# decaslime_mainboard_sch_easyeda.net
KiCad netlist of a schematic drawn in EasyEDA
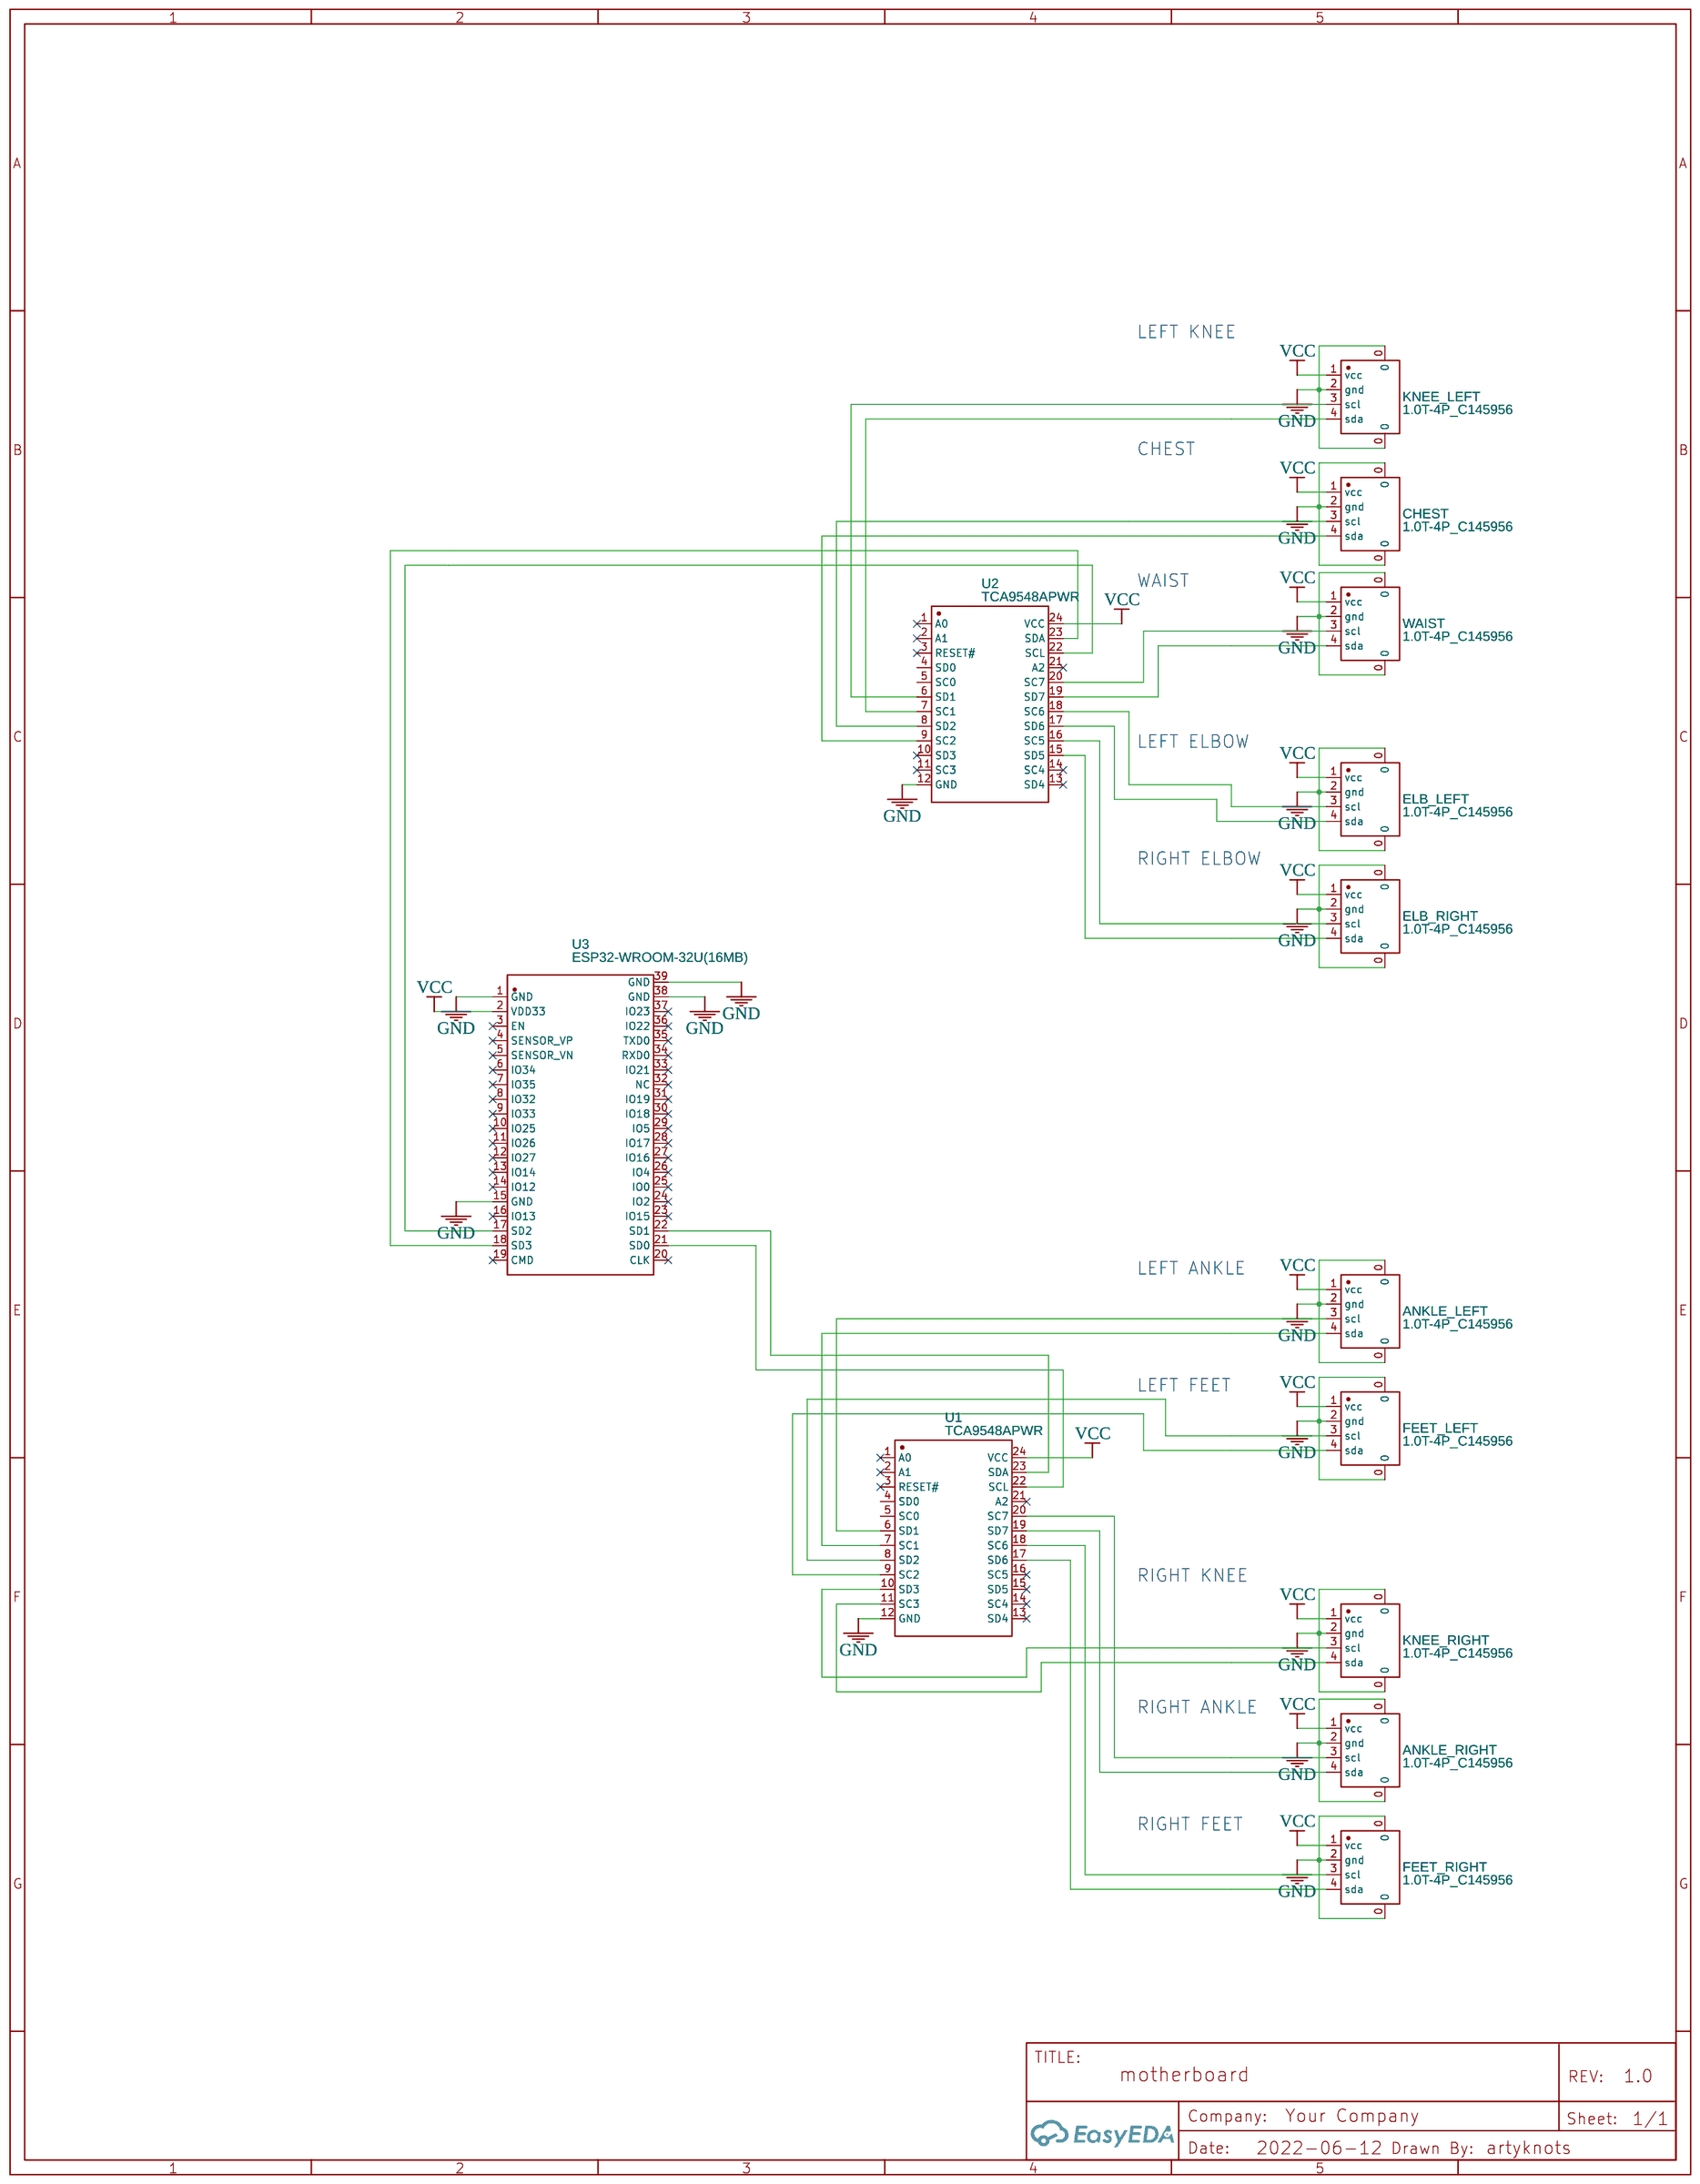
[diagram p0: schematic sheet]

(export (version "E")
  (design (tool "Eeschema 10.0.6"))
  (components
    (comp (ref "ANKLE_LEFT")
      (value "1.0T-4P_C145956")
      (fields (field (name "BOM_Supplier Part") "C145956"))
      (libsource (lib "") (part "1.0T-4P_C145956_7"))
    )
    (comp (ref "ANKLE_RIGHT")
      (value "1.0T-4P_C145956")
      (fields (field (name "BOM_Supplier Part") "C145956"))
      (libsource (lib "") (part "1.0T-4P_C145956_1"))
    )
    (comp (ref "CHEST")
      (value "1.0T-4P_C145956")
      (fields (field (name "BOM_Supplier Part") "C145956"))
      (libsource (lib "") (part "1.0T-4P_C145956_6"))
    )
    (comp (ref "ELB_LEFT")
      (value "1.0T-4P_C145956")
      (fields (field (name "BOM_Supplier Part") "C145956"))
      (libsource (lib "") (part "1.0T-4P_C145956"))
    )
    (comp (ref "ELB_RIGHT")
      (value "1.0T-4P_C145956")
      (fields (field (name "BOM_Supplier Part") "C145956"))
      (libsource (lib "") (part "1.0T-4P_C145956_5"))
    )
    (comp (ref "FEET_LEFT")
      (value "1.0T-4P_C145956")
      (fields (field (name "BOM_Supplier Part") "C145956"))
      (libsource (lib "") (part "1.0T-4P_C145956_2"))
    )
    (comp (ref "FEET_RIGHT")
      (value "1.0T-4P_C145956")
      (fields (field (name "BOM_Supplier Part") "C145956"))
      (libsource (lib "") (part "1.0T-4P_C145956_8"))
    )
    (comp (ref "KNEE_LEFT")
      (value "1.0T-4P_C145956")
      (fields (field (name "BOM_Supplier Part") "C145956"))
      (libsource (lib "") (part "1.0T-4P_C145956_3"))
    )
    (comp (ref "KNEE_RIGHT")
      (value "1.0T-4P_C145956")
      (fields (field (name "BOM_Supplier Part") "C145956"))
      (libsource (lib "") (part "1.0T-4P_C145956_9"))
    )
    (comp (ref "U1")
      (value "TCA9548APWR")
      (fields (field (name "BOM_Supplier Part") "C130026"))
      (libsource (lib "") (part "TCA9548APWR"))
    )
    (comp (ref "U2")
      (value "TCA9548APWR")
      (fields (field (name "BOM_Supplier Part") "C130026"))
      (libsource (lib "") (part "TCA9548APWR"))
    )
    (comp (ref "U3")
      (value "ESP32-WROOM-32U(16MB)")
      (fields (field (name "BOM_Supplier Part") "C529580"))
      (libsource (lib "") (part "ESP32-WROOM-32U(16MB)"))
    )
    (comp (ref "WAIST")
      (value "1.0T-4P_C145956")
      (fields (field (name "BOM_Supplier Part") "C145956"))
      (libsource (lib "") (part "1.0T-4P_C145956_4"))
    )
  )
  (nets
    (net (code "1") (name "GND") (class "Default")
      (node (ref "ANKLE_LEFT") (pin "0") (pinfunction "0_0") (pintype "unspecified"))
      (node (ref "ANKLE_LEFT") (pin "2") (pinfunction "gnd_2") (pintype "unspecified"))
      (node (ref "ANKLE_RIGHT") (pin "0") (pinfunction "0_0") (pintype "unspecified"))
      (node (ref "ANKLE_RIGHT") (pin "2") (pinfunction "gnd_2") (pintype "unspecified"))
      (node (ref "CHEST") (pin "0") (pinfunction "0_0") (pintype "unspecified"))
      (node (ref "CHEST") (pin "2") (pinfunction "gnd_2") (pintype "unspecified"))
      (node (ref "ELB_LEFT") (pin "0") (pinfunction "0_0") (pintype "unspecified"))
      (node (ref "ELB_LEFT") (pin "2") (pinfunction "gnd_2") (pintype "unspecified"))
      (node (ref "ELB_RIGHT") (pin "0") (pinfunction "0_0") (pintype "unspecified"))
      (node (ref "ELB_RIGHT") (pin "2") (pinfunction "gnd_2") (pintype "unspecified"))
      (node (ref "FEET_LEFT") (pin "0") (pinfunction "0_0") (pintype "unspecified"))
      (node (ref "FEET_LEFT") (pin "2") (pinfunction "gnd_2") (pintype "unspecified"))
      (node (ref "FEET_RIGHT") (pin "0") (pinfunction "0_0") (pintype "unspecified"))
      (node (ref "FEET_RIGHT") (pin "2") (pinfunction "gnd_2") (pintype "unspecified"))
      (node (ref "KNEE_LEFT") (pin "0") (pinfunction "0_0") (pintype "unspecified"))
      (node (ref "KNEE_LEFT") (pin "2") (pinfunction "gnd_2") (pintype "unspecified"))
      (node (ref "KNEE_RIGHT") (pin "0") (pinfunction "0_0") (pintype "unspecified"))
      (node (ref "KNEE_RIGHT") (pin "2") (pinfunction "gnd_2") (pintype "unspecified"))
      (node (ref "U1") (pin "12") (pinfunction "GND_12") (pintype "unspecified"))
      (node (ref "U2") (pin "12") (pinfunction "GND_12") (pintype "unspecified"))
      (node (ref "U3") (pin "1") (pinfunction "GND_1") (pintype "unspecified"))
      (node (ref "U3") (pin "15") (pinfunction "GND_15") (pintype "unspecified"))
      (node (ref "U3") (pin "38") (pinfunction "GND_38") (pintype "unspecified"))
      (node (ref "U3") (pin "39") (pinfunction "GND_39") (pintype "unspecified"))
      (node (ref "WAIST") (pin "0") (pinfunction "0_0") (pintype "unspecified"))
      (node (ref "WAIST") (pin "2") (pinfunction "gnd_2") (pintype "unspecified"))
    )
    (net (code "2") (name "Net-(ANKLE_LEFT-scl)") (class "Default")
      (node (ref "ANKLE_LEFT") (pin "3") (pinfunction "scl_3") (pintype "unspecified"))
      (node (ref "U1") (pin "6") (pinfunction "SD1_6") (pintype "unspecified"))
    )
    (net (code "3") (name "Net-(ANKLE_LEFT-sda)") (class "Default")
      (node (ref "ANKLE_LEFT") (pin "4") (pinfunction "sda_4") (pintype "unspecified"))
      (node (ref "U1") (pin "7") (pinfunction "SC1_7") (pintype "unspecified"))
    )
    (net (code "4") (name "Net-(ANKLE_RIGHT-scl)") (class "Default")
      (node (ref "ANKLE_RIGHT") (pin "3") (pinfunction "scl_3") (pintype "unspecified"))
      (node (ref "U1") (pin "20") (pinfunction "SC7_20") (pintype "unspecified"))
    )
    (net (code "5") (name "Net-(ANKLE_RIGHT-sda)") (class "Default")
      (node (ref "ANKLE_RIGHT") (pin "4") (pinfunction "sda_4") (pintype "unspecified"))
      (node (ref "U1") (pin "19") (pinfunction "SD7_19") (pintype "unspecified"))
    )
    (net (code "6") (name "Net-(CHEST-scl)") (class "Default")
      (node (ref "CHEST") (pin "3") (pinfunction "scl_3") (pintype "unspecified"))
      (node (ref "U2") (pin "8") (pinfunction "SD2_8") (pintype "unspecified"))
    )
    (net (code "7") (name "Net-(CHEST-sda)") (class "Default")
      (node (ref "CHEST") (pin "4") (pinfunction "sda_4") (pintype "unspecified"))
      (node (ref "U2") (pin "9") (pinfunction "SC2_9") (pintype "unspecified"))
    )
    (net (code "8") (name "Net-(ELB_LEFT-scl)") (class "Default")
      (node (ref "ELB_LEFT") (pin "3") (pinfunction "scl_3") (pintype "unspecified"))
      (node (ref "U2") (pin "18") (pinfunction "SC6_18") (pintype "unspecified"))
    )
    (net (code "9") (name "Net-(ELB_LEFT-sda)") (class "Default")
      (node (ref "ELB_LEFT") (pin "4") (pinfunction "sda_4") (pintype "unspecified"))
      (node (ref "U2") (pin "17") (pinfunction "SD6_17") (pintype "unspecified"))
    )
    (net (code "10") (name "Net-(ELB_RIGHT-scl)") (class "Default")
      (node (ref "ELB_RIGHT") (pin "3") (pinfunction "scl_3") (pintype "unspecified"))
      (node (ref "U2") (pin "16") (pinfunction "SC5_16") (pintype "unspecified"))
    )
    (net (code "11") (name "Net-(ELB_RIGHT-sda)") (class "Default")
      (node (ref "ELB_RIGHT") (pin "4") (pinfunction "sda_4") (pintype "unspecified"))
      (node (ref "U2") (pin "15") (pinfunction "SD5_15") (pintype "unspecified"))
    )
    (net (code "12") (name "Net-(FEET_LEFT-scl)") (class "Default")
      (node (ref "FEET_LEFT") (pin "3") (pinfunction "scl_3") (pintype "unspecified"))
      (node (ref "U1") (pin "8") (pinfunction "SD2_8") (pintype "unspecified"))
    )
    (net (code "13") (name "Net-(FEET_LEFT-sda)") (class "Default")
      (node (ref "FEET_LEFT") (pin "4") (pinfunction "sda_4") (pintype "unspecified"))
      (node (ref "U1") (pin "9") (pinfunction "SC2_9") (pintype "unspecified"))
    )
    (net (code "14") (name "Net-(FEET_RIGHT-scl)") (class "Default")
      (node (ref "FEET_RIGHT") (pin "3") (pinfunction "scl_3") (pintype "unspecified"))
      (node (ref "U1") (pin "18") (pinfunction "SC6_18") (pintype "unspecified"))
    )
    (net (code "15") (name "Net-(FEET_RIGHT-sda)") (class "Default")
      (node (ref "FEET_RIGHT") (pin "4") (pinfunction "sda_4") (pintype "unspecified"))
      (node (ref "U1") (pin "17") (pinfunction "SD6_17") (pintype "unspecified"))
    )
    (net (code "16") (name "Net-(KNEE_LEFT-scl)") (class "Default")
      (node (ref "KNEE_LEFT") (pin "3") (pinfunction "scl_3") (pintype "unspecified"))
      (node (ref "U2") (pin "6") (pinfunction "SD1_6") (pintype "unspecified"))
    )
    (net (code "17") (name "Net-(KNEE_LEFT-sda)") (class "Default")
      (node (ref "KNEE_LEFT") (pin "4") (pinfunction "sda_4") (pintype "unspecified"))
      (node (ref "U2") (pin "7") (pinfunction "SC1_7") (pintype "unspecified"))
    )
    (net (code "18") (name "Net-(KNEE_RIGHT-scl)") (class "Default")
      (node (ref "KNEE_RIGHT") (pin "3") (pinfunction "scl_3") (pintype "unspecified"))
      (node (ref "U1") (pin "10") (pinfunction "SD3_10") (pintype "unspecified"))
    )
    (net (code "19") (name "Net-(KNEE_RIGHT-sda)") (class "Default")
      (node (ref "KNEE_RIGHT") (pin "4") (pinfunction "sda_4") (pintype "unspecified"))
      (node (ref "U1") (pin "11") (pinfunction "SC3_11") (pintype "unspecified"))
    )
    (net (code "20") (name "Net-(U1-SCL)") (class "Default")
      (node (ref "U1") (pin "22") (pinfunction "SCL_22") (pintype "unspecified"))
      (node (ref "U3") (pin "21") (pinfunction "SD0_21") (pintype "unspecified"))
    )
    (net (code "21") (name "Net-(U1-SDA)") (class "Default")
      (node (ref "U1") (pin "23") (pinfunction "SDA_23") (pintype "unspecified"))
      (node (ref "U3") (pin "22") (pinfunction "SD1_22") (pintype "unspecified"))
    )
    (net (code "22") (name "Net-(U2-SC7)") (class "Default")
      (node (ref "U2") (pin "20") (pinfunction "SC7_20") (pintype "unspecified"))
      (node (ref "WAIST") (pin "3") (pinfunction "scl_3") (pintype "unspecified"))
    )
    (net (code "23") (name "Net-(U2-SCL)") (class "Default")
      (node (ref "U2") (pin "22") (pinfunction "SCL_22") (pintype "unspecified"))
      (node (ref "U3") (pin "17") (pinfunction "SD2_17") (pintype "unspecified"))
    )
    (net (code "24") (name "Net-(U2-SD7)") (class "Default")
      (node (ref "U2") (pin "19") (pinfunction "SD7_19") (pintype "unspecified"))
      (node (ref "WAIST") (pin "4") (pinfunction "sda_4") (pintype "unspecified"))
    )
    (net (code "25") (name "Net-(U2-SDA)") (class "Default")
      (node (ref "U2") (pin "23") (pinfunction "SDA_23") (pintype "unspecified"))
      (node (ref "U3") (pin "18") (pinfunction "SD3_18") (pintype "unspecified"))
    )
    (net (code "26") (name "VCC") (class "Default")
      (node (ref "ANKLE_LEFT") (pin "1") (pinfunction "vcc_1") (pintype "unspecified"))
      (node (ref "ANKLE_RIGHT") (pin "1") (pinfunction "vcc_1") (pintype "unspecified"))
      (node (ref "CHEST") (pin "1") (pinfunction "vcc_1") (pintype "unspecified"))
      (node (ref "ELB_LEFT") (pin "1") (pinfunction "vcc_1") (pintype "unspecified"))
      (node (ref "ELB_RIGHT") (pin "1") (pinfunction "vcc_1") (pintype "unspecified"))
      (node (ref "FEET_LEFT") (pin "1") (pinfunction "vcc_1") (pintype "unspecified"))
      (node (ref "FEET_RIGHT") (pin "1") (pinfunction "vcc_1") (pintype "unspecified"))
      (node (ref "KNEE_LEFT") (pin "1") (pinfunction "vcc_1") (pintype "unspecified"))
      (node (ref "KNEE_RIGHT") (pin "1") (pinfunction "vcc_1") (pintype "unspecified"))
      (node (ref "U1") (pin "24") (pinfunction "VCC_24") (pintype "unspecified"))
      (node (ref "U2") (pin "24") (pinfunction "VCC_24") (pintype "unspecified"))
      (node (ref "U3") (pin "2") (pinfunction "VDD33_2") (pintype "unspecified"))
      (node (ref "WAIST") (pin "1") (pinfunction "vcc_1") (pintype "unspecified"))
    )
    (net (code "27") (name "unconnected-(U1-A0-Pad1)") (class "Default")
      (node (ref "U1") (pin "1") (pinfunction "A0_1") (pintype "unspecified+no_connect"))
    )
    (net (code "28") (name "unconnected-(U1-A1-Pad2)") (class "Default")
      (node (ref "U1") (pin "2") (pinfunction "A1_2") (pintype "unspecified+no_connect"))
    )
    (net (code "29") (name "unconnected-(U1-A2-Pad21)") (class "Default")
      (node (ref "U1") (pin "21") (pinfunction "A2_21") (pintype "unspecified+no_connect"))
    )
    (net (code "30") (name "unconnected-(U1-RESET#-Pad3)") (class "Default")
      (node (ref "U1") (pin "3") (pinfunction "RESET#_3") (pintype "unspecified+no_connect"))
    )
    (net (code "31") (name "unconnected-(U1-SC0-Pad5)") (class "Default")
      (node (ref "U1") (pin "5") (pinfunction "SC0_5") (pintype "unspecified"))
    )
    (net (code "32") (name "unconnected-(U1-SC4-Pad14)") (class "Default")
      (node (ref "U1") (pin "14") (pinfunction "SC4_14") (pintype "unspecified+no_connect"))
    )
    (net (code "33") (name "unconnected-(U1-SC5-Pad16)") (class "Default")
      (node (ref "U1") (pin "16") (pinfunction "SC5_16") (pintype "unspecified+no_connect"))
    )
    (net (code "34") (name "unconnected-(U1-SD0-Pad4)") (class "Default")
      (node (ref "U1") (pin "4") (pinfunction "SD0_4") (pintype "unspecified"))
    )
    (net (code "35") (name "unconnected-(U1-SD4-Pad13)") (class "Default")
      (node (ref "U1") (pin "13") (pinfunction "SD4_13") (pintype "unspecified+no_connect"))
    )
    (net (code "36") (name "unconnected-(U1-SD5-Pad15)") (class "Default")
      (node (ref "U1") (pin "15") (pinfunction "SD5_15") (pintype "unspecified+no_connect"))
    )
    (net (code "37") (name "unconnected-(U2-A0-Pad1)") (class "Default")
      (node (ref "U2") (pin "1") (pinfunction "A0_1") (pintype "unspecified+no_connect"))
    )
    (net (code "38") (name "unconnected-(U2-A1-Pad2)") (class "Default")
      (node (ref "U2") (pin "2") (pinfunction "A1_2") (pintype "unspecified+no_connect"))
    )
    (net (code "39") (name "unconnected-(U2-A2-Pad21)") (class "Default")
      (node (ref "U2") (pin "21") (pinfunction "A2_21") (pintype "unspecified+no_connect"))
    )
    (net (code "40") (name "unconnected-(U2-RESET#-Pad3)") (class "Default")
      (node (ref "U2") (pin "3") (pinfunction "RESET#_3") (pintype "unspecified+no_connect"))
    )
    (net (code "41") (name "unconnected-(U2-SC0-Pad5)") (class "Default")
      (node (ref "U2") (pin "5") (pinfunction "SC0_5") (pintype "unspecified"))
    )
    (net (code "42") (name "unconnected-(U2-SC3-Pad11)") (class "Default")
      (node (ref "U2") (pin "11") (pinfunction "SC3_11") (pintype "unspecified+no_connect"))
    )
    (net (code "43") (name "unconnected-(U2-SC4-Pad14)") (class "Default")
      (node (ref "U2") (pin "14") (pinfunction "SC4_14") (pintype "unspecified+no_connect"))
    )
    (net (code "44") (name "unconnected-(U2-SD0-Pad4)") (class "Default")
      (node (ref "U2") (pin "4") (pinfunction "SD0_4") (pintype "unspecified"))
    )
    (net (code "45") (name "unconnected-(U2-SD3-Pad10)") (class "Default")
      (node (ref "U2") (pin "10") (pinfunction "SD3_10") (pintype "unspecified+no_connect"))
    )
    (net (code "46") (name "unconnected-(U2-SD4-Pad13)") (class "Default")
      (node (ref "U2") (pin "13") (pinfunction "SD4_13") (pintype "unspecified+no_connect"))
    )
    (net (code "47") (name "unconnected-(U3-CLK-Pad20)") (class "Default")
      (node (ref "U3") (pin "20") (pinfunction "CLK_20") (pintype "unspecified+no_connect"))
    )
    (net (code "48") (name "unconnected-(U3-CMD-Pad19)") (class "Default")
      (node (ref "U3") (pin "19") (pinfunction "CMD_19") (pintype "unspecified+no_connect"))
    )
    (net (code "49") (name "unconnected-(U3-EN-Pad3)") (class "Default")
      (node (ref "U3") (pin "3") (pinfunction "EN_3") (pintype "unspecified+no_connect"))
    )
    (net (code "50") (name "unconnected-(U3-IO0-Pad25)") (class "Default")
      (node (ref "U3") (pin "25") (pinfunction "IO0_25") (pintype "unspecified+no_connect"))
    )
    (net (code "51") (name "unconnected-(U3-IO2-Pad24)") (class "Default")
      (node (ref "U3") (pin "24") (pinfunction "IO2_24") (pintype "unspecified+no_connect"))
    )
    (net (code "52") (name "unconnected-(U3-IO4-Pad26)") (class "Default")
      (node (ref "U3") (pin "26") (pinfunction "IO4_26") (pintype "unspecified+no_connect"))
    )
    (net (code "53") (name "unconnected-(U3-IO5-Pad29)") (class "Default")
      (node (ref "U3") (pin "29") (pinfunction "IO5_29") (pintype "unspecified+no_connect"))
    )
    (net (code "54") (name "unconnected-(U3-IO12-Pad14)") (class "Default")
      (node (ref "U3") (pin "14") (pinfunction "IO12_14") (pintype "unspecified+no_connect"))
    )
    (net (code "55") (name "unconnected-(U3-IO13-Pad16)") (class "Default")
      (node (ref "U3") (pin "16") (pinfunction "IO13_16") (pintype "unspecified+no_connect"))
    )
    (net (code "56") (name "unconnected-(U3-IO14-Pad13)") (class "Default")
      (node (ref "U3") (pin "13") (pinfunction "IO14_13") (pintype "unspecified+no_connect"))
    )
    (net (code "57") (name "unconnected-(U3-IO15-Pad23)") (class "Default")
      (node (ref "U3") (pin "23") (pinfunction "IO15_23") (pintype "unspecified+no_connect"))
    )
    (net (code "58") (name "unconnected-(U3-IO16-Pad27)") (class "Default")
      (node (ref "U3") (pin "27") (pinfunction "IO16_27") (pintype "unspecified+no_connect"))
    )
    (net (code "59") (name "unconnected-(U3-IO17-Pad28)") (class "Default")
      (node (ref "U3") (pin "28") (pinfunction "IO17_28") (pintype "unspecified+no_connect"))
    )
    (net (code "60") (name "unconnected-(U3-IO18-Pad30)") (class "Default")
      (node (ref "U3") (pin "30") (pinfunction "IO18_30") (pintype "unspecified+no_connect"))
    )
    (net (code "61") (name "unconnected-(U3-IO19-Pad31)") (class "Default")
      (node (ref "U3") (pin "31") (pinfunction "IO19_31") (pintype "unspecified+no_connect"))
    )
    (net (code "62") (name "unconnected-(U3-IO21-Pad33)") (class "Default")
      (node (ref "U3") (pin "33") (pinfunction "IO21_33") (pintype "unspecified+no_connect"))
    )
    (net (code "63") (name "unconnected-(U3-IO22-Pad36)") (class "Default")
      (node (ref "U3") (pin "36") (pinfunction "IO22_36") (pintype "unspecified+no_connect"))
    )
    (net (code "64") (name "unconnected-(U3-IO23-Pad37)") (class "Default")
      (node (ref "U3") (pin "37") (pinfunction "IO23_37") (pintype "unspecified+no_connect"))
    )
    (net (code "65") (name "unconnected-(U3-IO25-Pad10)") (class "Default")
      (node (ref "U3") (pin "10") (pinfunction "IO25_10") (pintype "unspecified+no_connect"))
    )
    (net (code "66") (name "unconnected-(U3-IO26-Pad11)") (class "Default")
      (node (ref "U3") (pin "11") (pinfunction "IO26_11") (pintype "unspecified+no_connect"))
    )
    (net (code "67") (name "unconnected-(U3-IO27-Pad12)") (class "Default")
      (node (ref "U3") (pin "12") (pinfunction "IO27_12") (pintype "unspecified+no_connect"))
    )
    (net (code "68") (name "unconnected-(U3-IO32-Pad8)") (class "Default")
      (node (ref "U3") (pin "8") (pinfunction "IO32_8") (pintype "unspecified+no_connect"))
    )
    (net (code "69") (name "unconnected-(U3-IO33-Pad9)") (class "Default")
      (node (ref "U3") (pin "9") (pinfunction "IO33_9") (pintype "unspecified+no_connect"))
    )
    (net (code "70") (name "unconnected-(U3-IO34-Pad6)") (class "Default")
      (node (ref "U3") (pin "6") (pinfunction "IO34_6") (pintype "unspecified+no_connect"))
    )
    (net (code "71") (name "unconnected-(U3-IO35-Pad7)") (class "Default")
      (node (ref "U3") (pin "7") (pinfunction "IO35_7") (pintype "unspecified+no_connect"))
    )
    (net (code "72") (name "unconnected-(U3-NC-Pad32)") (class "Default")
      (node (ref "U3") (pin "32") (pinfunction "NC_32") (pintype "unspecified+no_connect"))
    )
    (net (code "73") (name "unconnected-(U3-RXD0-Pad34)") (class "Default")
      (node (ref "U3") (pin "34") (pinfunction "RXD0_34") (pintype "unspecified+no_connect"))
    )
    (net (code "74") (name "unconnected-(U3-SENSOR_VN-Pad5)") (class "Default")
      (node (ref "U3") (pin "5") (pinfunction "SENSOR_VN_5") (pintype "unspecified+no_connect"))
    )
    (net (code "75") (name "unconnected-(U3-SENSOR_VP-Pad4)") (class "Default")
      (node (ref "U3") (pin "4") (pinfunction "SENSOR_VP_4") (pintype "unspecified+no_connect"))
    )
    (net (code "76") (name "unconnected-(U3-TXD0-Pad35)") (class "Default")
      (node (ref "U3") (pin "35") (pinfunction "TXD0_35") (pintype "unspecified+no_connect"))
    )
  )
)
